# usb_key.net
KiCad netlist of a schematic drawn in EAGLE
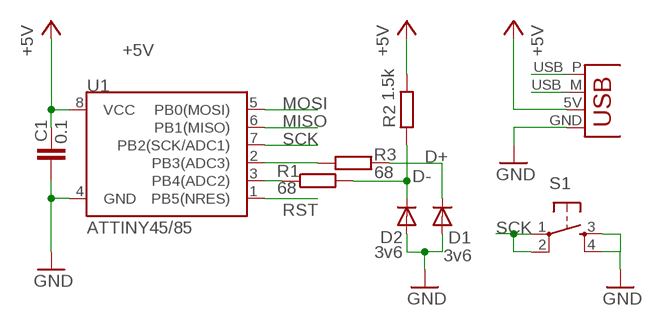
[diagram p0: schematic, sheet 1]

(export (version "E")
  (design (tool "Eeschema 10.0.6"))
  (components
    (comp (ref "C1")
      (value "0.1")
      (footprint "eagle-import:C0805")
      (libsource (lib "eagle-import") (part "C-EUC0805"))
    )
    (comp (ref "D1")
      (value "3v6")
      (footprint "eagle-import:MINIMELF")
      (libsource (lib "eagle-import") (part "DIODE-MINIMELF"))
    )
    (comp (ref "D2")
      (value "3v6")
      (footprint "eagle-import:MINIMELF")
      (libsource (lib "eagle-import") (part "DIODE-MINIMELF"))
    )
    (comp (ref "R1")
      (value "68")
      (footprint "eagle-import:R0805")
      (libsource (lib "eagle-import") (part "R-EU_R0805"))
    )
    (comp (ref "R2")
      (value "1.5k")
      (footprint "eagle-import:R0805")
      (libsource (lib "eagle-import") (part "R-EU_R0805"))
    )
    (comp (ref "R3")
      (value "68")
      (footprint "eagle-import:R0805")
      (libsource (lib "eagle-import") (part "R-EU_R0805"))
    )
    (comp (ref "S1")
      (value "TAC_SWITCHSMD")
      (footprint "eagle-import:TACTILE_SWITCH_SMD")
      (libsource (lib "eagle-import") (part "TAC_SWITCHSMD"))
    )
    (comp (ref "U1")
      (value "ATTINY45/85")
      (footprint "eagle-import:SO08-EIAJ")
      (libsource (lib "eagle-import") (part "ATTINY45"))
    )
    (comp (ref "X1")
      (value "USBPCB")
      (footprint "eagle-import:USB-A-PCB")
      (libsource (lib "eagle-import") (part "USBPCB"))
    )
  )
  (nets
    (net (code "1") (name "+5V") (class "Default")
      (node (ref "C1") (pin "1") (pinfunction "1_1") (pintype "passive"))
      (node (ref "R2") (pin "2") (pinfunction "2_2") (pintype "passive"))
      (node (ref "U1") (pin "8") (pinfunction "VCC_8") (pintype "bidirectional"))
      (node (ref "X1") (pin "5V") (pinfunction "VBUS_5V") (pintype "bidirectional"))
    )
    (net (code "2") (name "/D+") (class "Default")
      (node (ref "D1") (pin "C") (pinfunction "C_C") (pintype "passive"))
      (node (ref "R3") (pin "2") (pinfunction "2_2") (pintype "passive"))
    )
    (net (code "3") (name "/D-") (class "Default")
      (node (ref "D2") (pin "C") (pinfunction "C_C") (pintype "passive"))
      (node (ref "R1") (pin "2") (pinfunction "2_2") (pintype "passive"))
      (node (ref "R2") (pin "1") (pinfunction "1_1") (pintype "passive"))
    )
    (net (code "4") (name "/MISO") (class "Default")
      (node (ref "U1") (pin "6") (pinfunction "PB1(MISO)_6") (pintype "bidirectional"))
    )
    (net (code "5") (name "/MOSI") (class "Default")
      (node (ref "U1") (pin "5") (pinfunction "PB0(MOSI)_5") (pintype "bidirectional"))
    )
    (net (code "6") (name "/RST") (class "Default")
      (node (ref "U1") (pin "1") (pinfunction "PB5(NRES)_1") (pintype "bidirectional"))
    )
    (net (code "7") (name "/SCK") (class "Default")
      (node (ref "S1") (pin "1") (pinfunction "1_1") (pintype "passive"))
      (node (ref "S1") (pin "2") (pinfunction "2_2") (pintype "passive"))
      (node (ref "U1") (pin "7") (pinfunction "PB2(SCK/ADC1)_7") (pintype "bidirectional"))
    )
    (net (code "8") (name "GND") (class "Default")
      (node (ref "C1") (pin "2") (pinfunction "2_2") (pintype "passive"))
      (node (ref "D1") (pin "A") (pinfunction "A_A") (pintype "passive"))
      (node (ref "D2") (pin "A") (pinfunction "A_A") (pintype "passive"))
      (node (ref "S1") (pin "3") (pinfunction "3_3") (pintype "passive"))
      (node (ref "S1") (pin "4") (pinfunction "4_4") (pintype "passive"))
      (node (ref "U1") (pin "4") (pinfunction "GND_4") (pintype "bidirectional"))
      (node (ref "X1") (pin "GND") (pinfunction "GND_GND") (pintype "bidirectional"))
    )
    (net (code "9") (name "Net-(U1-PB3(ADC3))") (class "Default")
      (node (ref "R3") (pin "1") (pinfunction "1_1") (pintype "passive"))
      (node (ref "U1") (pin "2") (pinfunction "PB3(ADC3)_2") (pintype "bidirectional"))
    )
    (net (code "10") (name "Net-(U1-PB4(ADC2))") (class "Default")
      (node (ref "R1") (pin "1") (pinfunction "1_1") (pintype "passive"))
      (node (ref "U1") (pin "3") (pinfunction "PB4(ADC2)_3") (pintype "bidirectional"))
    )
    (net (code "11") (name "unconnected-(X1-D+-PadUSB_P)") (class "Default")
      (node (ref "X1") (pin "USB_P") (pinfunction "D+_USB_P") (pintype "bidirectional"))
    )
    (net (code "12") (name "unconnected-(X1-D--PadUSB_M)") (class "Default")
      (node (ref "X1") (pin "USB_M") (pinfunction "D-_USB_M") (pintype "bidirectional"))
    )
  )
)
